# Other.net
KiCad netlist of a schematic drawn in Altium Designer
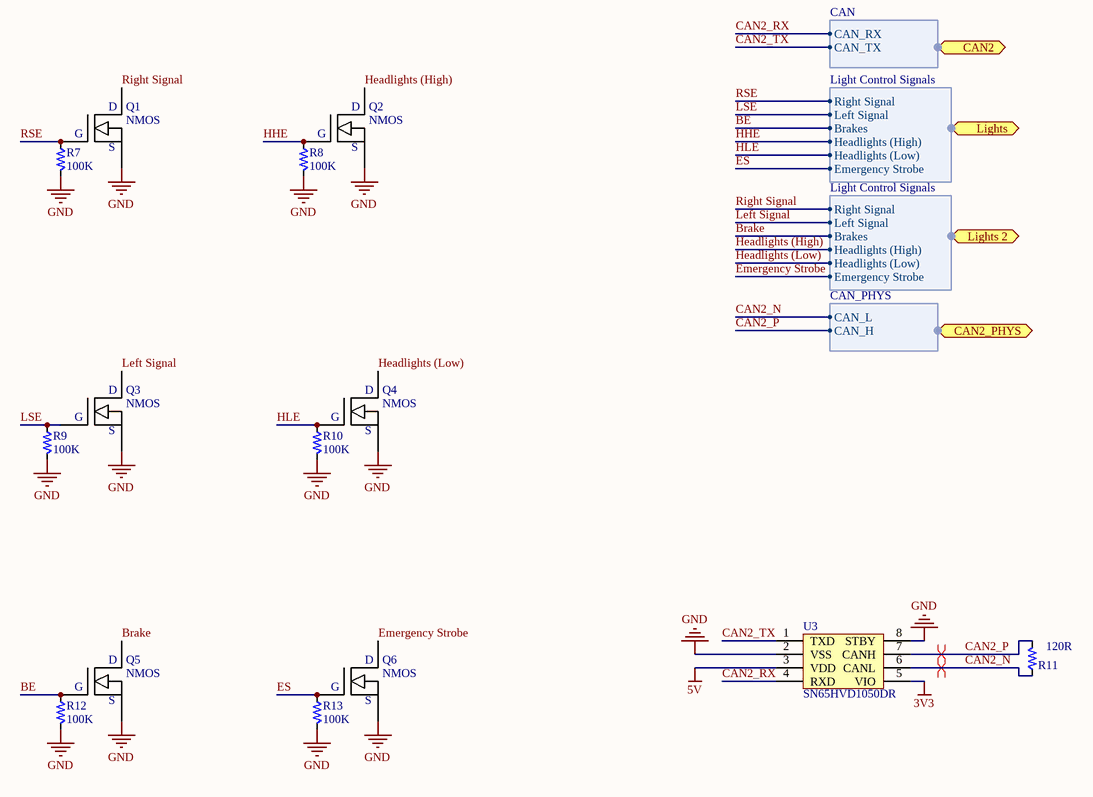
[diagram p0: Other.SchDoc]

(export (version "E")
  (design (tool "Eeschema 10.0.6"))
  (components
    (comp (ref "Q1")
      (value "NMOS")
      (footprint "NMOS - SSM3K333R - SOTFL95P180X88-3M")
      (libsource (lib "NMOS - SSM3K333R - SOTFL95P180X88-3M") (part "NMOS - SSM3K333R"))
    )
    (comp (ref "Q2")
      (value "NMOS")
      (footprint "NMOS - SSM3K333R - SOTFL95P180X88-3M")
      (libsource (lib "NMOS - SSM3K333R - SOTFL95P180X88-3M") (part "NMOS - SSM3K333R"))
    )
    (comp (ref "Q3")
      (value "NMOS")
      (footprint "NMOS - SSM3K333R - SOTFL95P180X88-3M")
      (libsource (lib "NMOS - SSM3K333R - SOTFL95P180X88-3M") (part "NMOS - SSM3K333R"))
    )
    (comp (ref "Q4")
      (value "NMOS")
      (footprint "NMOS - SSM3K333R - SOTFL95P180X88-3M")
      (libsource (lib "NMOS - SSM3K333R - SOTFL95P180X88-3M") (part "NMOS - SSM3K333R"))
    )
    (comp (ref "Q5")
      (value "NMOS")
      (footprint "NMOS - SSM3K333R - SOTFL95P180X88-3M")
      (libsource (lib "NMOS - SSM3K333R - SOTFL95P180X88-3M") (part "NMOS - SSM3K333R"))
    )
    (comp (ref "Q6")
      (value "NMOS")
      (footprint "NMOS - SSM3K333R - SOTFL95P180X88-3M")
      (libsource (lib "NMOS - SSM3K333R - SOTFL95P180X88-3M") (part "NMOS - SSM3K333R"))
    )
    (comp (ref "R7")
      (value "SCH_GENERIC_RESISTOR_0603")
      (footprint "PCB_GENERIC_SMD_0603")
      (description "Generic SMD resistor 0603")
      (fields (field (name "RESISTANCE") "100K"))
      (libsource (lib "SCH_GENERIC_RESISTOR_0603") (part "SCH_GENERIC_RESISTOR_0603"))
    )
    (comp (ref "R8")
      (value "SCH_GENERIC_RESISTOR_0603")
      (footprint "PCB_GENERIC_SMD_0603")
      (description "Generic SMD resistor 0603")
      (fields (field (name "RESISTANCE") "100K"))
      (libsource (lib "SCH_GENERIC_RESISTOR_0603") (part "SCH_GENERIC_RESISTOR_0603"))
    )
    (comp (ref "R9")
      (value "SCH_GENERIC_RESISTOR_0603")
      (footprint "PCB_GENERIC_SMD_0603")
      (description "Generic SMD resistor 0603")
      (fields (field (name "RESISTANCE") "100K"))
      (libsource (lib "SCH_GENERIC_RESISTOR_0603") (part "SCH_GENERIC_RESISTOR_0603"))
    )
    (comp (ref "R10")
      (value "SCH_GENERIC_RESISTOR_0603")
      (footprint "PCB_GENERIC_SMD_0603")
      (description "Generic SMD resistor 0603")
      (fields (field (name "RESISTANCE") "100K"))
      (libsource (lib "SCH_GENERIC_RESISTOR_0603") (part "SCH_GENERIC_RESISTOR_0603"))
    )
    (comp (ref "R11")
      (value "SCH_GENERIC_RESISTOR_0603")
      (footprint "PCB_GENERIC_SMD_0603")
      (description "Generic SMD resistor 0603")
      (fields (field (name "RESISTANCE") "120R"))
      (libsource (lib "Generic 0603 Resistor") (part "SCH_GENERIC_RESISTOR_0603"))
    )
    (comp (ref "R12")
      (value "SCH_GENERIC_RESISTOR_0603")
      (footprint "PCB_GENERIC_SMD_0603")
      (description "Generic SMD resistor 0603")
      (fields (field (name "RESISTANCE") "100K"))
      (libsource (lib "SCH_GENERIC_RESISTOR_0603") (part "SCH_GENERIC_RESISTOR_0603"))
    )
    (comp (ref "R13")
      (value "SCH_GENERIC_RESISTOR_0603")
      (footprint "PCB_GENERIC_SMD_0603")
      (description "Generic SMD resistor 0603")
      (fields (field (name "RESISTANCE") "100K"))
      (libsource (lib "SCH_GENERIC_RESISTOR_0603") (part "SCH_GENERIC_RESISTOR_0603"))
    )
    (comp (ref "U3")
      (value "SN65HVD1050DR")
      (footprint "SOIC127P600X175-8N")
      (description "IC EMC CAN TRANSCEIVER 8-SOIC")
      (libsource (lib "TI_SN65HVD1050DR") (part "SN65HVD1050DR"))
    )
  )
  (nets
    (net (code "6") (name "/BE") (class "Default")
      (node (ref "Q5") (pin "1") (pinfunction "G_1") (pintype "passive"))
      (node (ref "R12") (pin "1") (pinfunction "1_1") (pintype "passive"))
    )
    (net (code "7") (name "/Brake") (class "Default")
      (node (ref "Q5") (pin "3") (pinfunction "D_3") (pintype "passive"))
    )
    (net (code "8") (name "/CAN2_N") (class "Default")
      (node (ref "R11") (pin "1") (pinfunction "1_1") (pintype "passive"))
      (node (ref "U3") (pin "6") (pinfunction "CANL_6") (pintype "passive"))
    )
    (net (code "9") (name "/CAN2_P") (class "Default")
      (node (ref "R11") (pin "2") (pinfunction "2_2") (pintype "passive"))
      (node (ref "U3") (pin "7") (pinfunction "CANH_7") (pintype "passive"))
    )
    (net (code "10") (name "/CAN2_RX") (class "Default")
      (node (ref "U3") (pin "4") (pinfunction "RXD_4") (pintype "passive"))
    )
    (net (code "11") (name "/CAN2_TX") (class "Default")
      (node (ref "U3") (pin "1") (pinfunction "TXD_1") (pintype "passive"))
    )
    (net (code "12") (name "/ES") (class "Default")
      (node (ref "Q6") (pin "1") (pinfunction "G_1") (pintype "passive"))
      (node (ref "R13") (pin "1") (pinfunction "1_1") (pintype "passive"))
    )
    (net (code "13") (name "/Emergency Strobe") (class "Default")
      (node (ref "Q6") (pin "3") (pinfunction "D_3") (pintype "passive"))
    )
    (net (code "14") (name "/HHE") (class "Default")
      (node (ref "Q2") (pin "1") (pinfunction "G_1") (pintype "passive"))
      (node (ref "R8") (pin "1") (pinfunction "1_1") (pintype "passive"))
    )
    (net (code "15") (name "/HLE") (class "Default")
      (node (ref "Q4") (pin "1") (pinfunction "G_1") (pintype "passive"))
      (node (ref "R10") (pin "1") (pinfunction "1_1") (pintype "passive"))
    )
    (net (code "16") (name "/Headlights (High)") (class "Default")
      (node (ref "Q2") (pin "3") (pinfunction "D_3") (pintype "passive"))
    )
    (net (code "17") (name "/Headlights (Low)") (class "Default")
      (node (ref "Q4") (pin "3") (pinfunction "D_3") (pintype "passive"))
    )
    (net (code "18") (name "/LSE") (class "Default")
      (node (ref "Q3") (pin "1") (pinfunction "G_1") (pintype "passive"))
      (node (ref "R9") (pin "1") (pinfunction "1_1") (pintype "passive"))
    )
    (net (code "19") (name "/Left Signal") (class "Default")
      (node (ref "Q3") (pin "3") (pinfunction "D_3") (pintype "passive"))
    )
    (net (code "20") (name "/RSE") (class "Default")
      (node (ref "Q1") (pin "1") (pinfunction "G_1") (pintype "passive"))
      (node (ref "R7") (pin "1") (pinfunction "1_1") (pintype "passive"))
    )
    (net (code "21") (name "/Right Signal") (class "Default")
      (node (ref "Q1") (pin "3") (pinfunction "D_3") (pintype "passive"))
    )
    (net (code "25") (name "3V3") (class "Default")
      (node (ref "U3") (pin "5") (pinfunction "VIO_5") (pintype "passive"))
    )
    (net (code "26") (name "5V") (class "Default")
      (node (ref "U3") (pin "3") (pinfunction "VDD_3") (pintype "passive"))
    )
    (net (code "27") (name "GND") (class "Default")
      (node (ref "Q1") (pin "2") (pinfunction "S_2") (pintype "passive"))
      (node (ref "Q2") (pin "2") (pinfunction "S_2") (pintype "passive"))
      (node (ref "Q3") (pin "2") (pinfunction "S_2") (pintype "passive"))
      (node (ref "Q4") (pin "2") (pinfunction "S_2") (pintype "passive"))
      (node (ref "Q5") (pin "2") (pinfunction "S_2") (pintype "passive"))
      (node (ref "Q6") (pin "2") (pinfunction "S_2") (pintype "passive"))
      (node (ref "R10") (pin "2") (pinfunction "2_2") (pintype "passive"))
      (node (ref "R12") (pin "2") (pinfunction "2_2") (pintype "passive"))
      (node (ref "R13") (pin "2") (pinfunction "2_2") (pintype "passive"))
      (node (ref "R7") (pin "2") (pinfunction "2_2") (pintype "passive"))
      (node (ref "R8") (pin "2") (pinfunction "2_2") (pintype "passive"))
      (node (ref "R9") (pin "2") (pinfunction "2_2") (pintype "passive"))
      (node (ref "U3") (pin "2") (pinfunction "VSS_2") (pintype "passive"))
      (node (ref "U3") (pin "8") (pinfunction "STBY_8") (pintype "passive"))
    )
  )
)
